# untitled.net
KiCad netlist of a schematic drawn in EAGLE
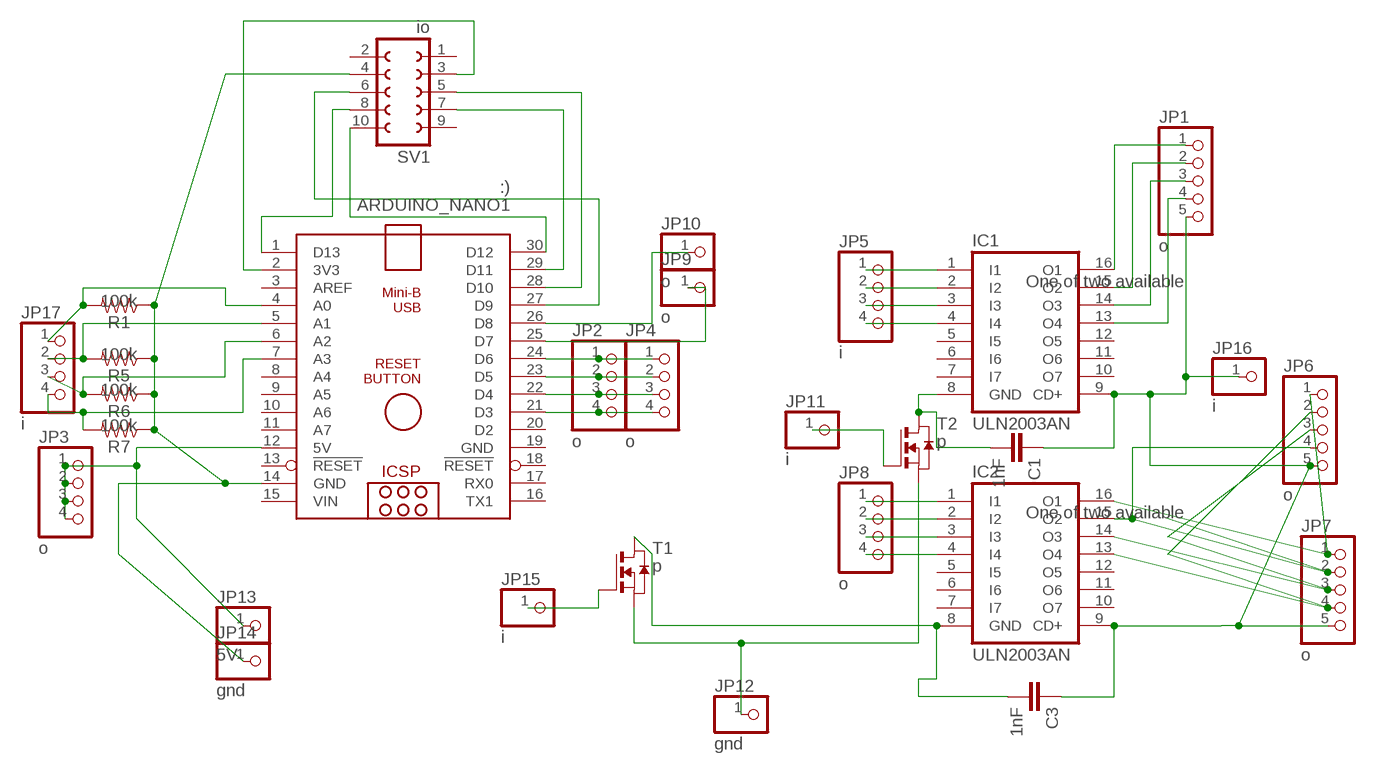
[diagram p0: schematic, sheet 1]

(export (version "E")
  (design (tool "Eeschema 10.0.6"))
  (components
    (comp (ref "ARDUINO_NANO1")
      (value ":)")
      (footprint "eagle-import:ARDUINO_NANO")
      (libsource (lib "eagle-import") (part "ARDUINO_NANO"))
    )
    (comp (ref "C1")
      (value "1nF")
      (footprint "eagle-import:0603")
      (libsource (lib "eagle-import") (part "1.0NF/1000PF-0603-50V-10%"))
    )
    (comp (ref "C3")
      (value "1nF")
      (footprint "eagle-import:0603")
      (libsource (lib "eagle-import") (part "1.0NF/1000PF-0603-50V-10%"))
    )
    (comp (ref "IC1")
      (value "ULN2003AN")
      (footprint "eagle-import:DIL16")
      (fields (field (name "A") "One of two available"))
      (libsource (lib "eagle-import") (part "ULN2003AN"))
    )
    (comp (ref "IC2")
      (value "ULN2003AN")
      (footprint "eagle-import:DIL16")
      (fields (field (name "A") "One of two available"))
      (libsource (lib "eagle-import") (part "ULN2003AN"))
    )
    (comp (ref "JP1")
      (value "o")
      (footprint "eagle-import:1X05")
      (libsource (lib "eagle-import") (part "PINHD-1X5"))
    )
    (comp (ref "JP2")
      (value "o")
      (footprint "eagle-import:1X04")
      (libsource (lib "eagle-import") (part "PINHD-1X4"))
    )
    (comp (ref "JP3")
      (value "o")
      (footprint "eagle-import:1X04")
      (libsource (lib "eagle-import") (part "PINHD-1X4"))
    )
    (comp (ref "JP4")
      (value "o")
      (footprint "eagle-import:1X04")
      (libsource (lib "eagle-import") (part "PINHD-1X4"))
    )
    (comp (ref "JP5")
      (value "i")
      (footprint "eagle-import:1X04")
      (libsource (lib "eagle-import") (part "PINHD-1X4"))
    )
    (comp (ref "JP6")
      (value "o")
      (footprint "eagle-import:1X05")
      (libsource (lib "eagle-import") (part "PINHD-1X5"))
    )
    (comp (ref "JP7")
      (value "o")
      (footprint "eagle-import:1X05")
      (libsource (lib "eagle-import") (part "PINHD-1X5"))
    )
    (comp (ref "JP8")
      (value "o")
      (footprint "eagle-import:1X04")
      (libsource (lib "eagle-import") (part "PINHD-1X4"))
    )
    (comp (ref "JP9")
      (value "o")
      (footprint "eagle-import:1X01")
      (libsource (lib "eagle-import") (part "PINHD-1X1"))
    )
    (comp (ref "JP10")
      (value "o")
      (footprint "eagle-import:1X01")
      (libsource (lib "eagle-import") (part "PINHD-1X1"))
    )
    (comp (ref "JP11")
      (value "i")
      (footprint "eagle-import:1X01")
      (libsource (lib "eagle-import") (part "PINHD-1X1"))
    )
    (comp (ref "JP12")
      (value "gnd")
      (footprint "eagle-import:1X01")
      (libsource (lib "eagle-import") (part "PINHD-1X1"))
    )
    (comp (ref "JP13")
      (value "5V")
      (footprint "eagle-import:1X01")
      (libsource (lib "eagle-import") (part "PINHD-1X1"))
    )
    (comp (ref "JP14")
      (value "gnd")
      (footprint "eagle-import:1X01")
      (libsource (lib "eagle-import") (part "PINHD-1X1"))
    )
    (comp (ref "JP15")
      (value "i")
      (footprint "eagle-import:1X01")
      (libsource (lib "eagle-import") (part "PINHD-1X1"))
    )
    (comp (ref "JP16")
      (value "i")
      (footprint "eagle-import:1X01")
      (libsource (lib "eagle-import") (part "PINHD-1X1"))
    )
    (comp (ref "JP17")
      (value "i")
      (footprint "eagle-import:1X04")
      (libsource (lib "eagle-import") (part "PINHD-1X4"))
    )
    (comp (ref "R1")
      (value "100k")
      (footprint "eagle-import:0603")
      (libsource (lib "eagle-import") (part "100KOHM-0603-1/10W-1%"))
    )
    (comp (ref "R5")
      (value "100k")
      (footprint "eagle-import:0603")
      (libsource (lib "eagle-import") (part "100KOHM-0603-1/10W-1%"))
    )
    (comp (ref "R6")
      (value "100k")
      (footprint "eagle-import:0603")
      (libsource (lib "eagle-import") (part "100KOHM-0603-1/10W-1%"))
    )
    (comp (ref "R7")
      (value "100k")
      (footprint "eagle-import:0603")
      (libsource (lib "eagle-import") (part "100KOHM-0603-1/10W-1%"))
    )
    (comp (ref "SV1")
      (value "io")
      (footprint "eagle-import:FE05-2")
      (libsource (lib "eagle-import") (part "FE05-2"))
    )
    (comp (ref "T1")
      (value "p")
      (footprint "eagle-import:SOT89")
      (libsource (lib "eagle-import") (part "NMOSSOT89"))
    )
    (comp (ref "T2")
      (value "p")
      (footprint "eagle-import:SOT89")
      (libsource (lib "eagle-import") (part "NMOSSOT89"))
    )
  )
  (nets
    (net (code "1") (name "/GND") (class "Default")
      (node (ref "ARDUINO_NANO1") (pin "19") (pinfunction "GND_19") (pintype "power_in"))
    )
    (net (code "2") (name "/VIN") (class "Default")
      (node (ref "ARDUINO_NANO1") (pin "15") (pinfunction "VIN_15") (pintype "power_in"))
    )
    (net (code "3") (name "Net-(ARDUINO_NANO1-3V3)") (class "Default")
      (node (ref "ARDUINO_NANO1") (pin "2") (pinfunction "3V3_2") (pintype "output"))
      (node (ref "SV1") (pin "3") (pinfunction "3_3") (pintype "passive"))
    )
    (net (code "4") (name "Net-(ARDUINO_NANO1-5V)") (class "Default")
      (node (ref "ARDUINO_NANO1") (pin "12") (pinfunction "5V_12") (pintype "power_in"))
      (node (ref "JP13") (pin "1") (pinfunction "1_1") (pintype "passive"))
      (node (ref "JP3") (pin "1") (pinfunction "1_1") (pintype "passive"))
      (node (ref "JP3") (pin "2") (pinfunction "2_2") (pintype "passive"))
      (node (ref "JP3") (pin "3") (pinfunction "3_3") (pintype "passive"))
      (node (ref "JP3") (pin "4") (pinfunction "4_4") (pintype "passive"))
    )
    (net (code "5") (name "Net-(ARDUINO_NANO1-A0)") (class "Default")
      (node (ref "ARDUINO_NANO1") (pin "4") (pinfunction "A0_4") (pintype "bidirectional"))
      (node (ref "JP17") (pin "1") (pinfunction "1_1") (pintype "passive"))
      (node (ref "R1") (pin "2") (pinfunction "2_2") (pintype "passive"))
    )
    (net (code "6") (name "Net-(ARDUINO_NANO1-A1)") (class "Default")
      (node (ref "ARDUINO_NANO1") (pin "5") (pinfunction "A1_5") (pintype "bidirectional"))
      (node (ref "JP17") (pin "2") (pinfunction "2_2") (pintype "passive"))
      (node (ref "R5") (pin "2") (pinfunction "2_2") (pintype "passive"))
    )
    (net (code "7") (name "Net-(ARDUINO_NANO1-A2)") (class "Default")
      (node (ref "ARDUINO_NANO1") (pin "6") (pinfunction "A2_6") (pintype "bidirectional"))
      (node (ref "JP17") (pin "3") (pinfunction "3_3") (pintype "passive"))
      (node (ref "R6") (pin "2") (pinfunction "2_2") (pintype "passive"))
    )
    (net (code "8") (name "Net-(ARDUINO_NANO1-A3)") (class "Default")
      (node (ref "ARDUINO_NANO1") (pin "7") (pinfunction "A3_7") (pintype "bidirectional"))
      (node (ref "JP17") (pin "4") (pinfunction "4_4") (pintype "passive"))
      (node (ref "R7") (pin "2") (pinfunction "2_2") (pintype "passive"))
    )
    (net (code "9") (name "Net-(ARDUINO_NANO1-D3)") (class "Default")
      (node (ref "ARDUINO_NANO1") (pin "21") (pinfunction "D3_21") (pintype "bidirectional"))
      (node (ref "JP2") (pin "4") (pinfunction "4_4") (pintype "passive"))
      (node (ref "JP4") (pin "4") (pinfunction "4_4") (pintype "passive"))
    )
    (net (code "10") (name "Net-(ARDUINO_NANO1-D4)") (class "Default")
      (node (ref "ARDUINO_NANO1") (pin "22") (pinfunction "D4_22") (pintype "bidirectional"))
      (node (ref "JP2") (pin "3") (pinfunction "3_3") (pintype "passive"))
      (node (ref "JP4") (pin "3") (pinfunction "3_3") (pintype "passive"))
    )
    (net (code "11") (name "Net-(ARDUINO_NANO1-D5)") (class "Default")
      (node (ref "ARDUINO_NANO1") (pin "23") (pinfunction "D5_23") (pintype "bidirectional"))
      (node (ref "JP2") (pin "2") (pinfunction "2_2") (pintype "passive"))
      (node (ref "JP4") (pin "2") (pinfunction "2_2") (pintype "passive"))
    )
    (net (code "12") (name "Net-(ARDUINO_NANO1-D6)") (class "Default")
      (node (ref "ARDUINO_NANO1") (pin "24") (pinfunction "D6_24") (pintype "bidirectional"))
      (node (ref "JP2") (pin "1") (pinfunction "1_1") (pintype "passive"))
      (node (ref "JP4") (pin "1") (pinfunction "1_1") (pintype "passive"))
    )
    (net (code "13") (name "Net-(ARDUINO_NANO1-D7)") (class "Default")
      (node (ref "ARDUINO_NANO1") (pin "25") (pinfunction "D7_25") (pintype "bidirectional"))
      (node (ref "JP9") (pin "1") (pinfunction "1_1") (pintype "passive"))
    )
    (net (code "14") (name "Net-(ARDUINO_NANO1-D8)") (class "Default")
      (node (ref "ARDUINO_NANO1") (pin "26") (pinfunction "D8_26") (pintype "bidirectional"))
      (node (ref "JP10") (pin "1") (pinfunction "1_1") (pintype "passive"))
    )
    (net (code "15") (name "Net-(ARDUINO_NANO1-D9)") (class "Default")
      (node (ref "ARDUINO_NANO1") (pin "27") (pinfunction "D9_27") (pintype "bidirectional"))
      (node (ref "SV1") (pin "6") (pinfunction "6_6") (pintype "passive"))
    )
    (net (code "16") (name "Net-(ARDUINO_NANO1-D10)") (class "Default")
      (node (ref "ARDUINO_NANO1") (pin "28") (pinfunction "D10_28") (pintype "bidirectional"))
      (node (ref "SV1") (pin "5") (pinfunction "5_5") (pintype "passive"))
    )
    (net (code "17") (name "Net-(ARDUINO_NANO1-D11)") (class "Default")
      (node (ref "ARDUINO_NANO1") (pin "29") (pinfunction "D11_29") (pintype "bidirectional"))
      (node (ref "SV1") (pin "7") (pinfunction "7_7") (pintype "passive"))
    )
    (net (code "18") (name "Net-(ARDUINO_NANO1-D12)") (class "Default")
      (node (ref "ARDUINO_NANO1") (pin "30") (pinfunction "D12_30") (pintype "bidirectional"))
      (node (ref "SV1") (pin "10") (pinfunction "10_10") (pintype "passive"))
    )
    (net (code "19") (name "Net-(ARDUINO_NANO1-D13)") (class "Default")
      (node (ref "ARDUINO_NANO1") (pin "1") (pinfunction "D13_1") (pintype "bidirectional"))
      (node (ref "SV1") (pin "8") (pinfunction "8_8") (pintype "passive"))
    )
    (net (code "20") (name "Net-(ARDUINO_NANO1-GND-Pad14)") (class "Default")
      (node (ref "ARDUINO_NANO1") (pin "14") (pinfunction "GND_14") (pintype "power_in"))
      (node (ref "JP14") (pin "1") (pinfunction "1_1") (pintype "passive"))
      (node (ref "R1") (pin "1") (pinfunction "1_1") (pintype "passive"))
      (node (ref "R5") (pin "1") (pinfunction "1_1") (pintype "passive"))
      (node (ref "R6") (pin "1") (pinfunction "1_1") (pintype "passive"))
      (node (ref "R7") (pin "1") (pinfunction "1_1") (pintype "passive"))
      (node (ref "SV1") (pin "4") (pinfunction "4_4") (pintype "passive"))
    )
    (net (code "21") (name "Net-(IC1-CD+)") (class "Default")
      (node (ref "C1") (pin "1") (pinfunction "1_1") (pintype "passive"))
      (node (ref "C3") (pin "1") (pinfunction "1_1") (pintype "passive"))
      (node (ref "IC1") (pin "9") (pinfunction "CD+_9") (pintype "passive"))
      (node (ref "IC2") (pin "9") (pinfunction "CD+_9") (pintype "passive"))
      (node (ref "JP1") (pin "5") (pinfunction "5_5") (pintype "passive"))
      (node (ref "JP16") (pin "1") (pinfunction "1_1") (pintype "passive"))
      (node (ref "JP6") (pin "5") (pinfunction "5_5") (pintype "passive"))
      (node (ref "JP7") (pin "5") (pinfunction "5_5") (pintype "passive"))
    )
    (net (code "22") (name "Net-(IC1-GND)") (class "Default")
      (node (ref "C1") (pin "2") (pinfunction "2_2") (pintype "passive"))
      (node (ref "IC1") (pin "8") (pinfunction "GND_8") (pintype "power_in"))
      (node (ref "T2") (pin "2") (pinfunction "D_2") (pintype "passive"))
      (node (ref "T2") (pin "2@1") (pinfunction "D_2@1") (pintype "passive"))
    )
    (net (code "23") (name "Net-(IC1-I1)") (class "Default")
      (node (ref "IC1") (pin "1") (pinfunction "I1_1") (pintype "input"))
      (node (ref "JP5") (pin "1") (pinfunction "1_1") (pintype "passive"))
    )
    (net (code "24") (name "Net-(IC1-I2)") (class "Default")
      (node (ref "IC1") (pin "2") (pinfunction "I2_2") (pintype "input"))
      (node (ref "JP5") (pin "2") (pinfunction "2_2") (pintype "passive"))
    )
    (net (code "25") (name "Net-(IC1-I3)") (class "Default")
      (node (ref "IC1") (pin "3") (pinfunction "I3_3") (pintype "input"))
      (node (ref "JP5") (pin "3") (pinfunction "3_3") (pintype "passive"))
    )
    (net (code "26") (name "Net-(IC1-I4)") (class "Default")
      (node (ref "IC1") (pin "4") (pinfunction "I4_4") (pintype "input"))
      (node (ref "JP5") (pin "4") (pinfunction "4_4") (pintype "passive"))
    )
    (net (code "27") (name "Net-(IC1-O1)") (class "Default")
      (node (ref "IC1") (pin "16") (pinfunction "O1_16") (pintype "open_collector"))
      (node (ref "JP1") (pin "1") (pinfunction "1_1") (pintype "passive"))
    )
    (net (code "28") (name "Net-(IC1-O2)") (class "Default")
      (node (ref "IC1") (pin "15") (pinfunction "O2_15") (pintype "open_collector"))
      (node (ref "JP1") (pin "2") (pinfunction "2_2") (pintype "passive"))
    )
    (net (code "29") (name "Net-(IC1-O3)") (class "Default")
      (node (ref "IC1") (pin "14") (pinfunction "O3_14") (pintype "open_collector"))
      (node (ref "JP1") (pin "3") (pinfunction "3_3") (pintype "passive"))
    )
    (net (code "30") (name "Net-(IC1-O4)") (class "Default")
      (node (ref "IC1") (pin "13") (pinfunction "O4_13") (pintype "open_collector"))
      (node (ref "JP1") (pin "4") (pinfunction "4_4") (pintype "passive"))
    )
    (net (code "31") (name "Net-(IC2-GND)") (class "Default")
      (node (ref "C3") (pin "2") (pinfunction "2_2") (pintype "passive"))
      (node (ref "IC2") (pin "8") (pinfunction "GND_8") (pintype "power_in"))
      (node (ref "T1") (pin "2") (pinfunction "D_2") (pintype "passive"))
      (node (ref "T1") (pin "2@1") (pinfunction "D_2@1") (pintype "passive"))
    )
    (net (code "32") (name "Net-(IC2-I1)") (class "Default")
      (node (ref "IC2") (pin "1") (pinfunction "I1_1") (pintype "input"))
      (node (ref "JP8") (pin "1") (pinfunction "1_1") (pintype "passive"))
    )
    (net (code "33") (name "Net-(IC2-I2)") (class "Default")
      (node (ref "IC2") (pin "2") (pinfunction "I2_2") (pintype "input"))
      (node (ref "JP8") (pin "2") (pinfunction "2_2") (pintype "passive"))
    )
    (net (code "34") (name "Net-(IC2-I3)") (class "Default")
      (node (ref "IC2") (pin "3") (pinfunction "I3_3") (pintype "input"))
      (node (ref "JP8") (pin "3") (pinfunction "3_3") (pintype "passive"))
    )
    (net (code "35") (name "Net-(IC2-I4)") (class "Default")
      (node (ref "IC2") (pin "4") (pinfunction "I4_4") (pintype "input"))
      (node (ref "JP8") (pin "4") (pinfunction "4_4") (pintype "passive"))
    )
    (net (code "36") (name "Net-(IC2-O1)") (class "Default")
      (node (ref "IC2") (pin "16") (pinfunction "O1_16") (pintype "open_collector"))
      (node (ref "JP6") (pin "1") (pinfunction "1_1") (pintype "passive"))
      (node (ref "JP7") (pin "1") (pinfunction "1_1") (pintype "passive"))
    )
    (net (code "37") (name "Net-(IC2-O2)") (class "Default")
      (node (ref "IC2") (pin "15") (pinfunction "O2_15") (pintype "open_collector"))
      (node (ref "JP6") (pin "4") (pinfunction "4_4") (pintype "passive"))
      (node (ref "JP7") (pin "2") (pinfunction "2_2") (pintype "passive"))
    )
    (net (code "38") (name "Net-(IC2-O3)") (class "Default")
      (node (ref "IC2") (pin "14") (pinfunction "O3_14") (pintype "open_collector"))
      (node (ref "JP6") (pin "3") (pinfunction "3_3") (pintype "passive"))
      (node (ref "JP7") (pin "3") (pinfunction "3_3") (pintype "passive"))
    )
    (net (code "39") (name "Net-(IC2-O4)") (class "Default")
      (node (ref "IC2") (pin "13") (pinfunction "O4_13") (pintype "open_collector"))
      (node (ref "JP6") (pin "2") (pinfunction "2_2") (pintype "passive"))
      (node (ref "JP7") (pin "4") (pinfunction "4_4") (pintype "passive"))
    )
    (net (code "40") (name "Net-(T1-G)") (class "Default")
      (node (ref "JP15") (pin "1") (pinfunction "1_1") (pintype "passive"))
      (node (ref "T1") (pin "1") (pinfunction "G_1") (pintype "passive"))
    )
    (net (code "41") (name "Net-(T1-S)") (class "Default")
      (node (ref "JP12") (pin "1") (pinfunction "1_1") (pintype "passive"))
      (node (ref "T1") (pin "3") (pinfunction "S_3") (pintype "passive"))
      (node (ref "T2") (pin "3") (pinfunction "S_3") (pintype "passive"))
    )
    (net (code "42") (name "Net-(T2-G)") (class "Default")
      (node (ref "JP11") (pin "1") (pinfunction "1_1") (pintype "passive"))
      (node (ref "T2") (pin "1") (pinfunction "G_1") (pintype "passive"))
    )
    (net (code "43") (name "unconnected-(ARDUINO_NANO1-A4-Pad8)") (class "Default")
      (node (ref "ARDUINO_NANO1") (pin "8") (pinfunction "A4_8") (pintype "bidirectional"))
    )
    (net (code "44") (name "unconnected-(ARDUINO_NANO1-A5-Pad9)") (class "Default")
      (node (ref "ARDUINO_NANO1") (pin "9") (pinfunction "A5_9") (pintype "bidirectional"))
    )
    (net (code "45") (name "unconnected-(ARDUINO_NANO1-A6-Pad10)") (class "Default")
      (node (ref "ARDUINO_NANO1") (pin "10") (pinfunction "A6_10") (pintype "bidirectional"))
    )
    (net (code "46") (name "unconnected-(ARDUINO_NANO1-A7-Pad11)") (class "Default")
      (node (ref "ARDUINO_NANO1") (pin "11") (pinfunction "A7_11") (pintype "bidirectional"))
    )
    (net (code "47") (name "unconnected-(ARDUINO_NANO1-AREF-Pad3)") (class "Default")
      (node (ref "ARDUINO_NANO1") (pin "3") (pinfunction "AREF_3") (pintype "input"))
    )
    (net (code "48") (name "unconnected-(ARDUINO_NANO1-D2-Pad20)") (class "Default")
      (node (ref "ARDUINO_NANO1") (pin "20") (pinfunction "D2_20") (pintype "bidirectional"))
    )
    (net (code "49") (name "unconnected-(ARDUINO_NANO1-RX0-Pad17)") (class "Default")
      (node (ref "ARDUINO_NANO1") (pin "17") (pinfunction "RX0_17") (pintype "bidirectional"))
    )
    (net (code "50") (name "unconnected-(ARDUINO_NANO1-TX1-Pad16)") (class "Default")
      (node (ref "ARDUINO_NANO1") (pin "16") (pinfunction "TX1_16") (pintype "bidirectional"))
    )
    (net (code "51") (name "unconnected-(ARDUINO_NANO1-~{RESET}-Pad13)") (class "Default")
      (node (ref "ARDUINO_NANO1") (pin "13") (pinfunction "~{RESET}_13") (pintype "input"))
    )
    (net (code "52") (name "unconnected-(ARDUINO_NANO1-~{RESET}-Pad18)") (class "Default")
      (node (ref "ARDUINO_NANO1") (pin "18") (pinfunction "~{RESET}_18") (pintype "input"))
    )
    (net (code "53") (name "unconnected-(IC1-I5-Pad5)") (class "Default")
      (node (ref "IC1") (pin "5") (pinfunction "I5_5") (pintype "input"))
    )
    (net (code "54") (name "unconnected-(IC1-I6-Pad6)") (class "Default")
      (node (ref "IC1") (pin "6") (pinfunction "I6_6") (pintype "input"))
    )
    (net (code "55") (name "unconnected-(IC1-I7-Pad7)") (class "Default")
      (node (ref "IC1") (pin "7") (pinfunction "I7_7") (pintype "input"))
    )
    (net (code "56") (name "unconnected-(IC1-O5-Pad12)") (class "Default")
      (node (ref "IC1") (pin "12") (pinfunction "O5_12") (pintype "open_collector"))
    )
    (net (code "57") (name "unconnected-(IC1-O6-Pad11)") (class "Default")
      (node (ref "IC1") (pin "11") (pinfunction "O6_11") (pintype "open_collector"))
    )
    (net (code "58") (name "unconnected-(IC1-O7-Pad10)") (class "Default")
      (node (ref "IC1") (pin "10") (pinfunction "O7_10") (pintype "open_collector"))
    )
    (net (code "59") (name "unconnected-(IC2-I5-Pad5)") (class "Default")
      (node (ref "IC2") (pin "5") (pinfunction "I5_5") (pintype "input"))
    )
    (net (code "60") (name "unconnected-(IC2-I6-Pad6)") (class "Default")
      (node (ref "IC2") (pin "6") (pinfunction "I6_6") (pintype "input"))
    )
    (net (code "61") (name "unconnected-(IC2-I7-Pad7)") (class "Default")
      (node (ref "IC2") (pin "7") (pinfunction "I7_7") (pintype "input"))
    )
    (net (code "62") (name "unconnected-(IC2-O5-Pad12)") (class "Default")
      (node (ref "IC2") (pin "12") (pinfunction "O5_12") (pintype "open_collector"))
    )
    (net (code "63") (name "unconnected-(IC2-O6-Pad11)") (class "Default")
      (node (ref "IC2") (pin "11") (pinfunction "O6_11") (pintype "open_collector"))
    )
    (net (code "64") (name "unconnected-(IC2-O7-Pad10)") (class "Default")
      (node (ref "IC2") (pin "10") (pinfunction "O7_10") (pintype "open_collector"))
    )
    (net (code "65") (name "unconnected-(SV1-Pad1)") (class "Default")
      (node (ref "SV1") (pin "1") (pinfunction "1_1") (pintype "passive"))
    )
    (net (code "66") (name "unconnected-(SV1-Pad2)") (class "Default")
      (node (ref "SV1") (pin "2") (pinfunction "2_2") (pintype "passive"))
    )
    (net (code "67") (name "unconnected-(SV1-Pad9)") (class "Default")
      (node (ref "SV1") (pin "9") (pinfunction "9_9") (pintype "passive"))
    )
  )
)
